# CarteTxMoteur.net
KiCad netlist of a schematic drawn in Altium Designer
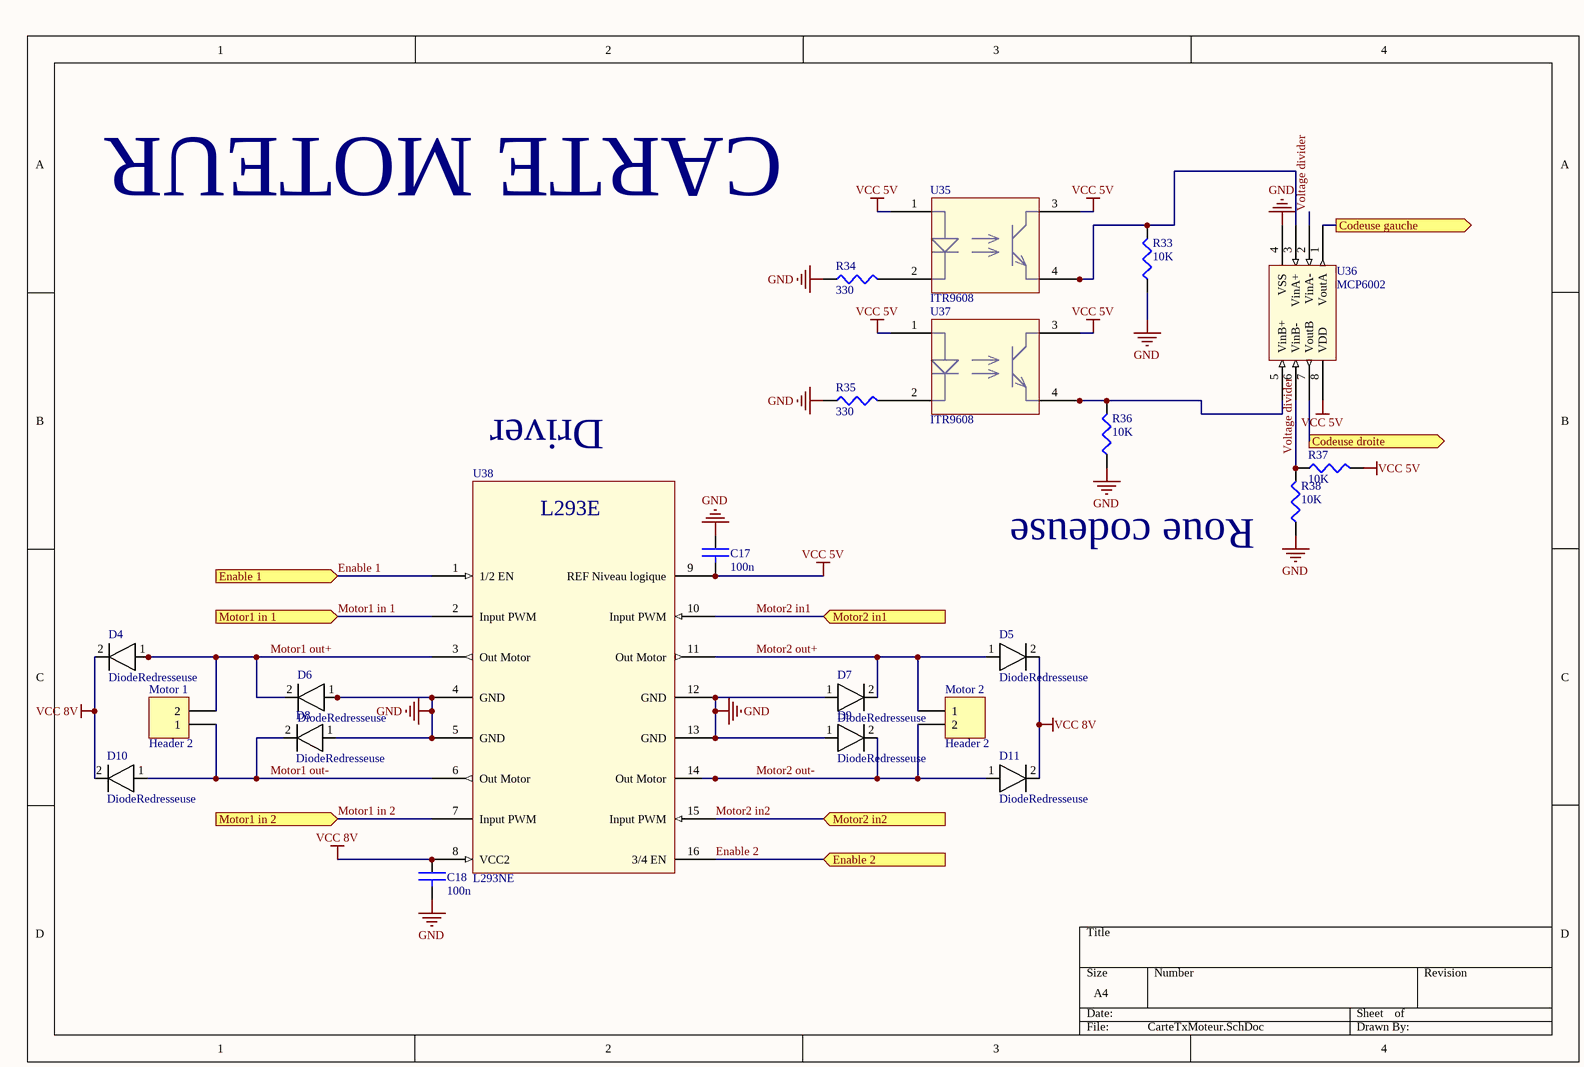
[diagram p0: CarteTxMoteur.SchDoc]

(export (version "E")
  (design (tool "Eeschema 10.0.6"))
  (components
    (comp (ref "C17")
      (value "100n")
      (footprint "0805")
      (description "capacité non polarisée")
      (fields (field (name "Comment") "CAP"))
      (libsource (lib "ISEN_basics_26-05-2015") (part "CAP"))
    )
    (comp (ref "C18")
      (value "100n")
      (footprint "0805")
      (description "capacité non polarisée")
      (fields (field (name "Comment") "CAP"))
      (libsource (lib "ISEN_basics_26-05-2015") (part "CAP"))
    )
    (comp (ref "D4")
      (value "DiodeRedresseuse")
      (footprint "Diode MULTICOMP SS16")
      (libsource (lib "Diode") (part "DiodeRedresseuse"))
    )
    (comp (ref "D5")
      (value "DiodeRedresseuse")
      (footprint "Diode MULTICOMP SS16")
      (libsource (lib "Diode") (part "DiodeRedresseuse"))
    )
    (comp (ref "D6")
      (value "DiodeRedresseuse")
      (footprint "Diode MULTICOMP SS16")
      (libsource (lib "Diode") (part "DiodeRedresseuse"))
    )
    (comp (ref "D7")
      (value "DiodeRedresseuse")
      (footprint "Diode MULTICOMP SS16")
      (libsource (lib "Diode") (part "DiodeRedresseuse"))
    )
    (comp (ref "D8")
      (value "DiodeRedresseuse")
      (footprint "Diode MULTICOMP SS16")
      (libsource (lib "Diode") (part "DiodeRedresseuse"))
    )
    (comp (ref "D9")
      (value "DiodeRedresseuse")
      (footprint "Diode MULTICOMP SS16")
      (libsource (lib "Diode") (part "DiodeRedresseuse"))
    )
    (comp (ref "D10")
      (value "DiodeRedresseuse")
      (footprint "Diode MULTICOMP SS16")
      (libsource (lib "Diode") (part "DiodeRedresseuse"))
    )
    (comp (ref "D11")
      (value "DiodeRedresseuse")
      (footprint "Diode MULTICOMP SS16")
      (libsource (lib "Diode") (part "DiodeRedresseuse"))
    )
    (comp (ref "Motor 1")
      (value "Header 2")
      (footprint "HDR1X2")
      (description "Header, 2-Pin")
      (fields (field (name "PUBLISHER") "Altium Limited"))
      (libsource (lib "") (part "Header 2_1"))
    )
    (comp (ref "Motor 2")
      (value "Header 2")
      (footprint "HDR1X2")
      (description "Header, 2-Pin")
      (fields (field (name "PUBLISHER") "Altium Limited"))
      (libsource (lib "Miscellaneous Connectors") (part "Header 2"))
    )
    (comp (ref "R33")
      (value "10K")
      (footprint "0805")
      (description "resistance")
      (fields (field (name "Comment") "RES"))
      (libsource (lib "ISEN_basics_26-05-2015") (part "RES"))
    )
    (comp (ref "R34")
      (value "330")
      (footprint "0805")
      (description "resistance")
      (fields (field (name "Comment") "RES"))
      (libsource (lib "ISEN_basics_26-05-2015") (part "RES"))
    )
    (comp (ref "R35")
      (value "330")
      (footprint "0805")
      (description "resistance")
      (fields (field (name "Comment") "RES"))
      (libsource (lib "ISEN_basics_26-05-2015") (part "RES"))
    )
    (comp (ref "R36")
      (value "10K")
      (footprint "0805")
      (description "resistance")
      (fields (field (name "Comment") "RES"))
      (libsource (lib "ISEN_basics_26-05-2015") (part "RES"))
    )
    (comp (ref "R37")
      (value "10K")
      (footprint "0805")
      (description "resistance")
      (fields (field (name "Comment") "RES"))
      (libsource (lib "ISEN_basics_26-05-2015") (part "RES"))
    )
    (comp (ref "R38")
      (value "10K")
      (footprint "0805")
      (description "resistance")
      (fields (field (name "Comment") "RES"))
      (libsource (lib "ISEN_basics_26-05-2015") (part "RES"))
    )
    (comp (ref "U35")
      (value "ITR9608")
      (footprint "ITR9608 footprint")
      (description "Intersection sensor")
      (libsource (lib "ITR9608") (part "ITR9608"))
    )
    (comp (ref "U36")
      (value "MCP6002")
      (footprint "MCP6002")
      (description "Double Operational Amplifier")
      (libsource (lib "MCP6002") (part "MCP6002"))
    )
    (comp (ref "U37")
      (value "ITR9608")
      (footprint "ITR9608 footprint")
      (description "Intersection sensor")
      (libsource (lib "ITR9608") (part "ITR9608"))
    )
    (comp (ref "U38") (value "L293NE") (footprint "L293NE") (libsource (lib "L293NE") (part "L293NE")))
  )
  (nets
    (net (code "1") (name "/Codeuse droite") (class "Default")
      (node (ref "U36") (pin "7") (pinfunction "VoutB_7") (pintype "output"))
    )
    (net (code "2") (name "/Codeuse gauche") (class "Default")
      (node (ref "U36") (pin "1") (pinfunction "VoutA_1") (pintype "output"))
    )
    (net (code "3") (name "/Enable 1") (class "Default")
      (node (ref "U38") (pin "1") (pinfunction "1/2_EN_1") (pintype "input"))
    )
    (net (code "4") (name "/Enable 2") (class "Default")
      (node (ref "U38") (pin "16") (pinfunction "3/4_EN_16") (pintype "passive"))
    )
    (net (code "5") (name "/Motor1 in 1") (class "Default")
      (node (ref "U38") (pin "2") (pinfunction "Input_PWM_2") (pintype "passive"))
    )
    (net (code "6") (name "/Motor1 in 2") (class "Default")
      (node (ref "U38") (pin "7") (pinfunction "Input_PWM_7") (pintype "passive"))
    )
    (net (code "7") (name "/Motor1 out+") (class "Default")
      (node (ref "D4") (pin "1") (pinfunction "1_1") (pintype "passive"))
      (node (ref "D6") (pin "2") (pinfunction "2_2") (pintype "passive"))
      (node (ref "Motor 1") (pin "2") (pinfunction "2_2") (pintype "passive"))
      (node (ref "U38") (pin "3") (pinfunction "Out_Motor_3") (pintype "output"))
    )
    (net (code "8") (name "/Motor1 out-") (class "Default")
      (node (ref "D10") (pin "1") (pinfunction "1_1") (pintype "passive"))
      (node (ref "D8") (pin "2") (pinfunction "2_2") (pintype "passive"))
      (node (ref "Motor 1") (pin "1") (pinfunction "1_1") (pintype "passive"))
      (node (ref "U38") (pin "6") (pinfunction "Out_Motor_6") (pintype "output"))
    )
    (net (code "9") (name "/Motor2 in1") (class "Default")
      (node (ref "U38") (pin "10") (pinfunction "Input_PWM_10") (pintype "input"))
    )
    (net (code "10") (name "/Motor2 in2") (class "Default")
      (node (ref "U38") (pin "15") (pinfunction "Input_PWM_15") (pintype "input"))
    )
    (net (code "11") (name "/Motor2 out+") (class "Default")
      (node (ref "D5") (pin "1") (pinfunction "1_1") (pintype "passive"))
      (node (ref "D7") (pin "2") (pinfunction "2_2") (pintype "passive"))
      (node (ref "Motor 2") (pin "1") (pinfunction "1_1") (pintype "passive"))
      (node (ref "U38") (pin "11") (pinfunction "Out_Motor_11") (pintype "output"))
    )
    (net (code "12") (name "/Motor2 out-") (class "Default")
      (node (ref "D11") (pin "1") (pinfunction "1_1") (pintype "passive"))
      (node (ref "D9") (pin "2") (pinfunction "2_2") (pintype "passive"))
      (node (ref "Motor 2") (pin "2") (pinfunction "2_2") (pintype "passive"))
      (node (ref "U38") (pin "14") (pinfunction "Out_Motor_14") (pintype "passive"))
    )
    (net (code "13") (name "/Voltage divider") (class "Default")
      (node (ref "R37") (pin "1") (pintype "passive"))
      (node (ref "R38") (pin "2") (pintype "passive"))
      (node (ref "U36") (pin "2") (pinfunction "VinA-_2") (pintype "input"))
      (node (ref "U36") (pin "6") (pinfunction "VinB-_6") (pintype "input"))
    )
    (net (code "14") (name "GND") (class "Default")
      (node (ref "C17") (pin "1") (pinfunction "1_1") (pintype "passive"))
      (node (ref "C18") (pin "2") (pinfunction "2_2") (pintype "passive"))
      (node (ref "D6") (pin "1") (pinfunction "1_1") (pintype "passive"))
      (node (ref "D7") (pin "1") (pinfunction "1_1") (pintype "passive"))
      (node (ref "D8") (pin "1") (pinfunction "1_1") (pintype "passive"))
      (node (ref "D9") (pin "1") (pinfunction "1_1") (pintype "passive"))
      (node (ref "R33") (pin "1") (pintype "passive"))
      (node (ref "R34") (pin "1") (pintype "passive"))
      (node (ref "R35") (pin "1") (pintype "passive"))
      (node (ref "R36") (pin "1") (pintype "passive"))
      (node (ref "R38") (pin "1") (pintype "passive"))
      (node (ref "U36") (pin "4") (pinfunction "VSS_4") (pintype "power_in"))
      (node (ref "U38") (pin "12") (pinfunction "GND_12") (pintype "passive"))
      (node (ref "U38") (pin "13") (pinfunction "GND_13") (pintype "passive"))
      (node (ref "U38") (pin "4") (pinfunction "GND_4") (pintype "passive"))
      (node (ref "U38") (pin "5") (pinfunction "GND_5") (pintype "passive"))
    )
    (net (code "15") (name "Net-(U35-Ld_Cathode)") (class "Default")
      (node (ref "R34") (pin "2") (pintype "passive"))
      (node (ref "U35") (pin "2") (pinfunction "Ld_Cathode_2") (pintype "passive"))
    )
    (net (code "16") (name "Net-(U35-Tr_Emitter)") (class "Default")
      (node (ref "R33") (pin "2") (pintype "passive"))
      (node (ref "U35") (pin "4") (pinfunction "Tr_Emitter_4") (pintype "passive"))
      (node (ref "U36") (pin "3") (pinfunction "VinA+_3") (pintype "input"))
    )
    (net (code "17") (name "Net-(U36-VinB+)") (class "Default")
      (node (ref "R36") (pin "2") (pintype "passive"))
      (node (ref "U36") (pin "5") (pinfunction "VinB+_5") (pintype "input"))
      (node (ref "U37") (pin "4") (pinfunction "Tr_Emitter_4") (pintype "passive"))
    )
    (net (code "18") (name "Net-(U37-Ld_Cathode)") (class "Default")
      (node (ref "R35") (pin "2") (pintype "passive"))
      (node (ref "U37") (pin "2") (pinfunction "Ld_Cathode_2") (pintype "passive"))
    )
    (net (code "19") (name "VCC 5V") (class "Default")
      (node (ref "C17") (pin "2") (pinfunction "2_2") (pintype "passive"))
      (node (ref "R37") (pin "2") (pintype "passive"))
      (node (ref "U35") (pin "1") (pinfunction "Ld_Anode_1") (pintype "passive"))
      (node (ref "U35") (pin "3") (pinfunction "Tr_Collector_3") (pintype "passive"))
      (node (ref "U36") (pin "8") (pinfunction "VDD_8") (pintype "power_in"))
      (node (ref "U37") (pin "1") (pinfunction "Ld_Anode_1") (pintype "passive"))
      (node (ref "U37") (pin "3") (pinfunction "Tr_Collector_3") (pintype "passive"))
      (node (ref "U38") (pin "9") (pinfunction "REF_Niveau_logique_9") (pintype "passive"))
    )
    (net (code "20") (name "VCC 8V") (class "Default")
      (node (ref "C18") (pin "1") (pinfunction "1_1") (pintype "passive"))
      (node (ref "D10") (pin "2") (pinfunction "2_2") (pintype "passive"))
      (node (ref "D11") (pin "2") (pinfunction "2_2") (pintype "passive"))
      (node (ref "D4") (pin "2") (pinfunction "2_2") (pintype "passive"))
      (node (ref "D5") (pin "2") (pinfunction "2_2") (pintype "passive"))
      (node (ref "U38") (pin "8") (pinfunction "VCC2_8") (pintype "input"))
    )
  )
)
